# Kicker.net
KiCad netlist of a schematic drawn in EAGLE
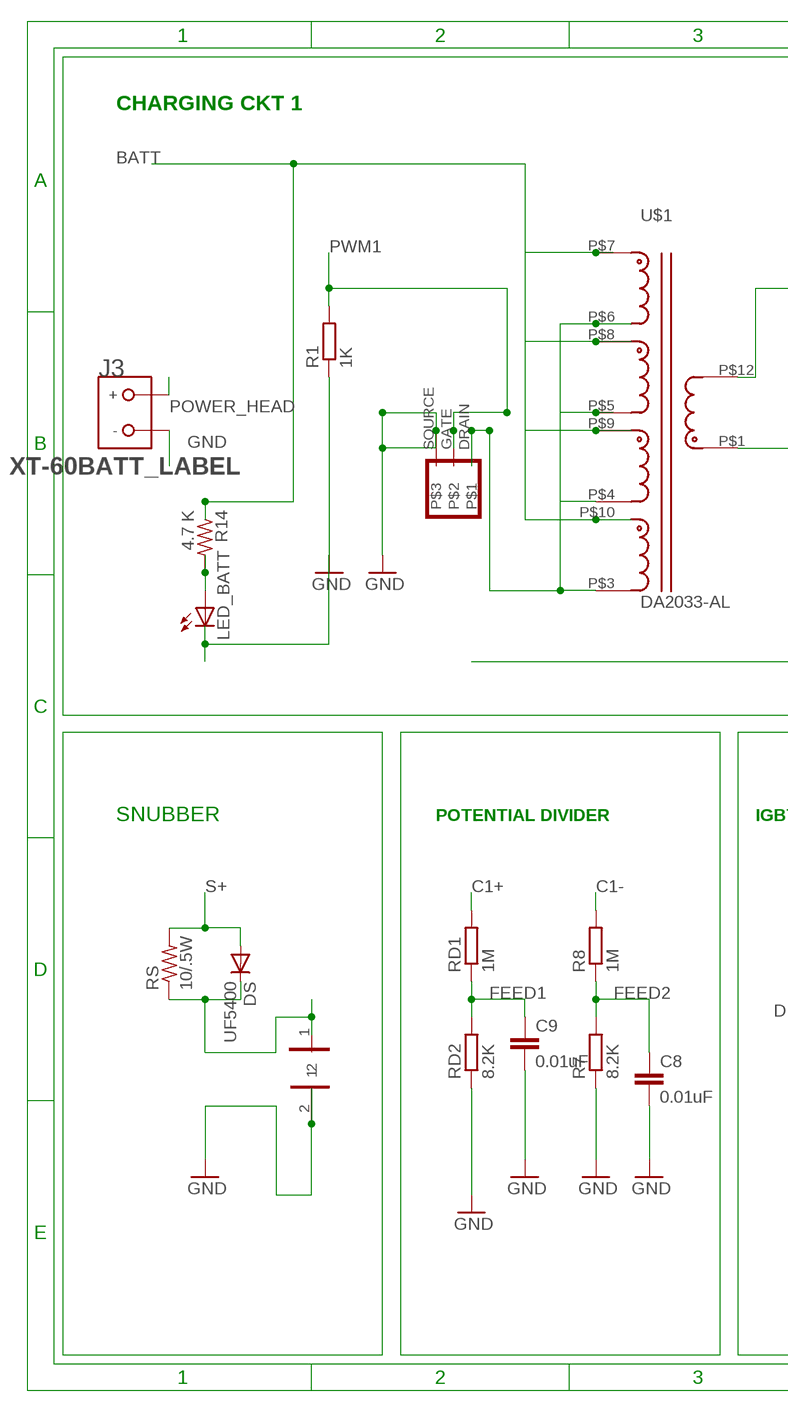
[diagram p0: schematic, sheet 1, part 1 of 2]
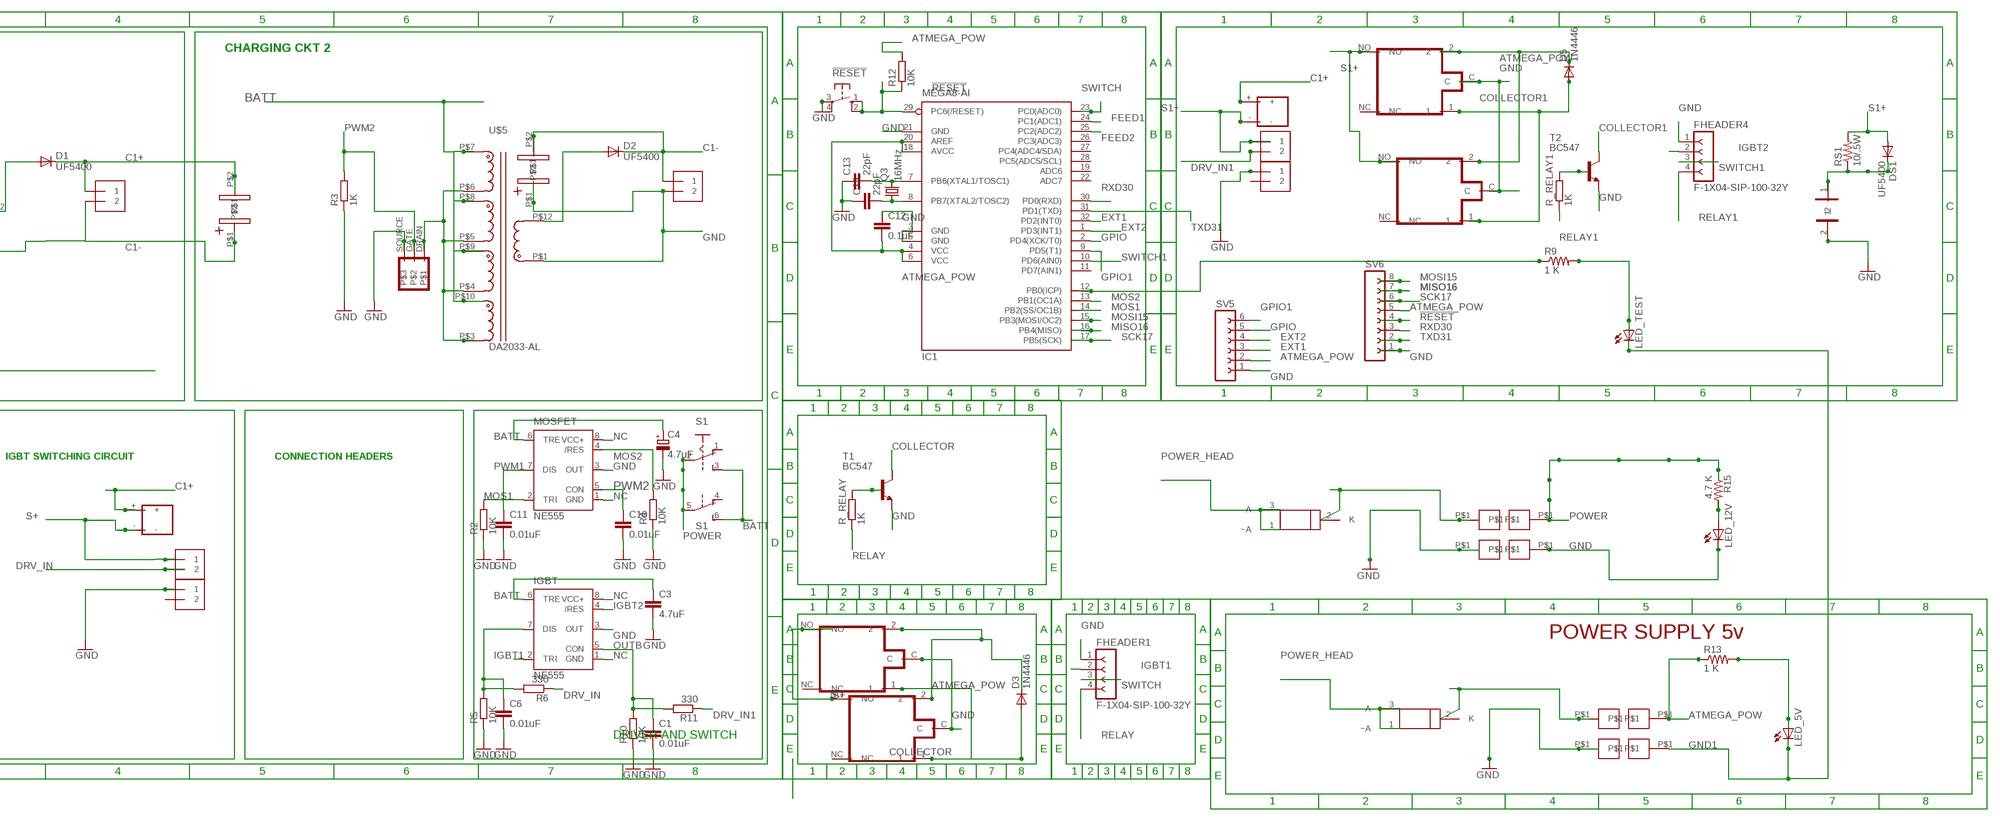
[diagram p1: schematic, sheet 1, part 2 of 2]

(export (version "E")
  (design (tool "Eeschema 10.0.6"))
  (components
    (comp (ref "!RESET")
      (value "10-XX")
      (footprint "eagle-import:B3F-10XX")
      (fields (field (name "MPN") "B3F-1000"))
      (libsource (lib "eagle-import") (part "10-XX"))
    )
    (comp (ref "5V")
      (value "PINHEAD_1")
      (footprint "eagle-import:PINHEAD_1")
      (libsource (lib "eagle-import") (part "PINHEAD_1"))
    )
    (comp (ref "C1")
      (value "0.01uF")
      (footprint "eagle-import:C1206")
      (libsource (lib "eagle-import") (part "C-EUC1206"))
    )
    (comp (ref "C3")
      (value "4.7uF")
      (footprint "eagle-import:C1206")
      (libsource (lib "eagle-import") (part "C-EUC1206"))
    )
    (comp (ref "C4")
      (value "4.7uF")
      (footprint "eagle-import:E2,5-6")
      (libsource (lib "eagle-import") (part "CPOL-EUE2.5-6"))
    )
    (comp (ref "C6")
      (value "0.01uF")
      (footprint "eagle-import:C1206")
      (libsource (lib "eagle-import") (part "C-EUC1206"))
    )
    (comp (ref "C8")
      (value "0.01uF")
      (footprint "eagle-import:C1206")
      (libsource (lib "eagle-import") (part "C-EUC1206"))
    )
    (comp (ref "C9")
      (value "0.01uF")
      (footprint "eagle-import:C1206")
      (libsource (lib "eagle-import") (part "C-EUC1206"))
    )
    (comp (ref "C10")
      (value "0.01uF")
      (footprint "eagle-import:C1206")
      (libsource (lib "eagle-import") (part "C-EUC1206"))
    )
    (comp (ref "C11")
      (value "0.01uF")
      (footprint "eagle-import:C1206")
      (libsource (lib "eagle-import") (part "C-EUC1206"))
    )
    (comp (ref "C12")
      (value "0.1uF")
      (footprint "eagle-import:C1206")
      (libsource (lib "eagle-import") (part "C-EUC1206"))
    )
    (comp (ref "C13")
      (value "22pF")
      (footprint "eagle-import:C1206")
      (libsource (lib "eagle-import") (part "C-EUC1206"))
    )
    (comp (ref "C14")
      (value "22pF")
      (footprint "eagle-import:C1206")
      (libsource (lib "eagle-import") (part "C-EUC1206"))
    )
    (comp (ref "D1")
      (value "UF5400")
      (footprint "eagle-import:DO201-15")
      (libsource (lib "eagle-import") (part "UF5400"))
    )
    (comp (ref "D2")
      (value "UF5400")
      (footprint "eagle-import:DO201-15")
      (libsource (lib "eagle-import") (part "UF5400"))
    )
    (comp (ref "D3")
      (value "1N4446")
      (footprint "eagle-import:DO35-10")
      (libsource (lib "eagle-import") (part "1N4446"))
    )
    (comp (ref "D5")
      (value "1N4446")
      (footprint "eagle-import:DO35-10")
      (libsource (lib "eagle-import") (part "1N4446"))
    )
    (comp (ref "DS")
      (value "UF5400")
      (footprint "eagle-import:DO201-15")
      (libsource (lib "eagle-import") (part "UF5400"))
    )
    (comp (ref "DS1")
      (value "UF5400")
      (footprint "eagle-import:DO201-15")
      (libsource (lib "eagle-import") (part "UF5400"))
    )
    (comp (ref "FHEADER1")
      (value "F-1X04-SIP-100-32Y")
      (footprint "eagle-import:SIP-100-04-32Y")
      (libsource (lib "eagle-import") (part "F-1X04-SIP-100-32Y"))
    )
    (comp (ref "FHEADER4")
      (value "F-1X04-SIP-100-32Y")
      (footprint "eagle-import:SIP-100-04-32Y")
      (libsource (lib "eagle-import") (part "F-1X04-SIP-100-32Y"))
    )
    (comp (ref "GND")
      (value "PINHEAD_1")
      (footprint "eagle-import:PINHEAD_1")
      (libsource (lib "eagle-import") (part "PINHEAD_1"))
    )
    (comp (ref "GND12")
      (value "PINHEAD_1")
      (footprint "eagle-import:PINHEAD_1")
      (libsource (lib "eagle-import") (part "PINHEAD_1"))
    )
    (comp (ref "GND_5V")
      (value "PINHEAD_1")
      (footprint "eagle-import:PINHEAD_1")
      (libsource (lib "eagle-import") (part "PINHEAD_1"))
    )
    (comp (ref "GND_12V1")
      (value "PINHEAD_1")
      (footprint "eagle-import:PINHEAD_1")
      (libsource (lib "eagle-import") (part "PINHEAD_1"))
    )
    (comp (ref "IC1")
      (value "MEGA8-AI")
      (footprint "eagle-import:TQFP32-08")
      (fields (field (name "MPN") "ATMEGA8-16AU"))
      (libsource (lib "eagle-import") (part "MEGA8-AI"))
    )
    (comp (ref "IGBT")
      (value "NE555")
      (footprint "eagle-import:DIL-08")
      (fields (field (name "MF") "Arrow Electronics") (field (name "MPN") "NE555N"))
      (libsource (lib "eagle-import") (part "NE555"))
    )
    (comp (ref "J1")
      (value "1X2-3.5MM")
      (footprint "eagle-import:1X2-3.5MM")
      (libsource (lib "eagle-import") (part "1X2-3.5MM"))
    )
    (comp (ref "J2")
      (value "1X2-3.5MM")
      (footprint "eagle-import:1X2-3.5MM")
      (libsource (lib "eagle-import") (part "1X2-3.5MM"))
    )
    (comp (ref "J3")
      (value "XT-60BATT_LABEL")
      (footprint "eagle-import:XT-60")
      (libsource (lib "eagle-import") (part "XT-60BATT_LABEL"))
    )
    (comp (ref "J4")
      (value "1X2-3.5MM")
      (footprint "eagle-import:1X2-3.5MM")
      (libsource (lib "eagle-import") (part "1X2-3.5MM"))
    )
    (comp (ref "J5")
      (value "1X2-3.5MM")
      (footprint "eagle-import:1X2-3.5MM")
      (libsource (lib "eagle-import") (part "1X2-3.5MM"))
    )
    (comp (ref "J6")
      (value "1X2-3.5MM")
      (footprint "eagle-import:1X2-3.5MM")
      (libsource (lib "eagle-import") (part "1X2-3.5MM"))
    )
    (comp (ref "J7")
      (value "1X2-3.5MM")
      (footprint "eagle-import:1X2-3.5MM")
      (libsource (lib "eagle-import") (part "1X2-3.5MM"))
    )
    (comp (ref "LED_5V")
      (value "LEDSML1206")
      (footprint "eagle-import:SML1206")
      (libsource (lib "eagle-import") (part "LEDSML1206"))
    )
    (comp (ref "LED_12V")
      (value "LEDSML1206")
      (footprint "eagle-import:SML1206")
      (libsource (lib "eagle-import") (part "LEDSML1206"))
    )
    (comp (ref "LED_BATT")
      (value "LEDSML1206")
      (footprint "eagle-import:SML1206")
      (libsource (lib "eagle-import") (part "LEDSML1206"))
    )
    (comp (ref "LED_TEST")
      (value "LEDSML1206")
      (footprint "eagle-import:SML1206")
      (libsource (lib "eagle-import") (part "LEDSML1206"))
    )
    (comp (ref "MOSFET")
      (value "NE555")
      (footprint "eagle-import:DIL-08")
      (fields (field (name "MF") "Arrow Electronics") (field (name "MPN") "NE555N"))
      (libsource (lib "eagle-import") (part "NE555"))
    )
    (comp (ref "POWER_1")
      (value "PINHEAD_1")
      (footprint "eagle-import:PINHEAD_1")
      (libsource (lib "eagle-import") (part "PINHEAD_1"))
    )
    (comp (ref "POWER_HEAD1")
      (value "PINHEAD_1")
      (footprint "eagle-import:PINHEAD_1")
      (libsource (lib "eagle-import") (part "PINHEAD_1"))
    )
    (comp (ref "Q3")
      (value "16MHz")
      (footprint "eagle-import:HC49U70")
      (libsource (lib "eagle-import") (part "CRYSTALHC49U70"))
    )
    (comp (ref "R1")
      (value "1K")
      (footprint "eagle-import:R1206")
      (libsource (lib "eagle-import") (part "R-EU_R1206"))
    )
    (comp (ref "R2")
      (value "10K")
      (footprint "eagle-import:R1206")
      (libsource (lib "eagle-import") (part "R-EU_R1206"))
    )
    (comp (ref "R3")
      (value "1K")
      (footprint "eagle-import:R1206")
      (libsource (lib "eagle-import") (part "R-EU_R1206"))
    )
    (comp (ref "R4")
      (value "10K")
      (footprint "eagle-import:R1206")
      (libsource (lib "eagle-import") (part "R-EU_R1206"))
    )
    (comp (ref "R5")
      (value "10K")
      (footprint "eagle-import:R1206")
      (libsource (lib "eagle-import") (part "R-EU_R1206"))
    )
    (comp (ref "R6")
      (value "330")
      (footprint "eagle-import:R1206")
      (libsource (lib "eagle-import") (part "R-EU_R1206"))
    )
    (comp (ref "R7")
      (value "8.2K")
      (footprint "eagle-import:R1206")
      (libsource (lib "eagle-import") (part "R-EU_R1206"))
    )
    (comp (ref "R8")
      (value "1M")
      (footprint "eagle-import:R1206")
      (libsource (lib "eagle-import") (part "R-EU_R1206"))
    )
    (comp (ref "R9")
      (value "1 K")
      (footprint "eagle-import:0805-THM")
      (libsource (lib "eagle-import") (part "FLIPFLOP-RES"))
    )
    (comp (ref "R10")
      (value "10K")
      (footprint "eagle-import:R1206")
      (libsource (lib "eagle-import") (part "R-EU_R1206"))
    )
    (comp (ref "R11")
      (value "330")
      (footprint "eagle-import:R1206")
      (libsource (lib "eagle-import") (part "R-EU_R1206"))
    )
    (comp (ref "R12")
      (value "10K")
      (footprint "eagle-import:R1206")
      (libsource (lib "eagle-import") (part "R-EU_R1206"))
    )
    (comp (ref "R13")
      (value "1 K")
      (footprint "eagle-import:0805-THM")
      (libsource (lib "eagle-import") (part "FLIPFLOP-RES"))
    )
    (comp (ref "R14")
      (value "4.7 K")
      (footprint "eagle-import:0805-THM")
      (libsource (lib "eagle-import") (part "FLIPFLOP-RES"))
    )
    (comp (ref "R15")
      (value "4.7 K")
      (footprint "eagle-import:0805-THM")
      (libsource (lib "eagle-import") (part "FLIPFLOP-RES"))
    )
    (comp (ref "RD1")
      (value "1M")
      (footprint "eagle-import:R1206")
      (libsource (lib "eagle-import") (part "R-EU_R1206"))
    )
    (comp (ref "RD2")
      (value "8.2K")
      (footprint "eagle-import:R1206")
      (libsource (lib "eagle-import") (part "R-EU_R1206"))
    )
    (comp (ref "RS")
      (value "10/.5W")
      (footprint "eagle-import:0411_15")
      (libsource (lib "eagle-import") (part "R-US_0411/15"))
    )
    (comp (ref "RS1")
      (value "10/.5W")
      (footprint "eagle-import:0411_15")
      (libsource (lib "eagle-import") (part "R-US_0411/15"))
    )
    (comp (ref "R_RELAY")
      (value "1K")
      (footprint "eagle-import:R1206")
      (libsource (lib "eagle-import") (part "R-EU_R1206"))
    )
    (comp (ref "R_RELAY1")
      (value "1K")
      (footprint "eagle-import:R1206")
      (libsource (lib "eagle-import") (part "R-EU_R1206"))
    )
    (comp (ref "S1")
      (value "A68-A31")
      (footprint "eagle-import:A68-A31")
      (libsource (lib "eagle-import") (part "A68-A31"))
    )
    (comp (ref "SV5")
      (value "FE06-1")
      (footprint "eagle-import:FE06")
      (libsource (lib "eagle-import") (part "FE06-1"))
    )
    (comp (ref "SV6")
      (value "FE08-1")
      (footprint "eagle-import:FE08")
      (libsource (lib "eagle-import") (part "FE08-1"))
    )
    (comp (ref "T1")
      (value "BC547")
      (footprint "eagle-import:TO92")
      (libsource (lib "eagle-import") (part "BC547"))
    )
    (comp (ref "T2")
      (value "BC547")
      (footprint "eagle-import:TO92")
      (libsource (lib "eagle-import") (part "BC547"))
    )
    (comp (ref "U$1")
      (value "DA2033-AL")
      (footprint "eagle-import:DA2033-AL")
      (libsource (lib "eagle-import") (part "DA2033-AL"))
    )
    (comp (ref "U$2")
      (value "CAPS")
      (footprint "eagle-import:CAP")
      (libsource (lib "eagle-import") (part "CAPS"))
    )
    (comp (ref "U$3")
      (value "MOS")
      (footprint "eagle-import:MOS")
      (libsource (lib "eagle-import") (part "MOS"))
    )
    (comp (ref "U$4")
      (value "CAPS")
      (footprint "eagle-import:CAP")
      (libsource (lib "eagle-import") (part "CAPS"))
    )
    (comp (ref "U$5")
      (value "DA2033-AL")
      (footprint "eagle-import:DA2033-AL")
      (libsource (lib "eagle-import") (part "DA2033-AL"))
    )
    (comp (ref "U$6")
      (value "SCREW")
      (footprint "eagle-import:SCREW")
      (libsource (lib "eagle-import") (part "SCREW"))
    )
    (comp (ref "U$7")
      (value "POLYCAP")
      (footprint "eagle-import:POLYCAP")
      (libsource (lib "eagle-import") (part "POLYCAP"))
    )
    (comp (ref "U$8")
      (value "POLYCAP")
      (footprint "eagle-import:POLYCAP")
      (libsource (lib "eagle-import") (part "POLYCAP"))
    )
    (comp (ref "U$9")
      (value "MOS")
      (footprint "eagle-import:MOS")
      (libsource (lib "eagle-import") (part "MOS"))
    )
    (comp (ref "U$10")
      (value "REL")
      (footprint "eagle-import:REL")
      (libsource (lib "eagle-import") (part "REL"))
    )
    (comp (ref "U$11")
      (value "REL")
      (footprint "eagle-import:REL")
      (libsource (lib "eagle-import") (part "REL"))
    )
    (comp (ref "U$12")
      (value "REL")
      (footprint "eagle-import:REL")
      (libsource (lib "eagle-import") (part "REL"))
    )
    (comp (ref "U$13")
      (value "REL")
      (footprint "eagle-import:REL")
      (libsource (lib "eagle-import") (part "REL"))
    )
    (comp (ref "U$16")
      (value "SCREW")
      (footprint "eagle-import:SCREW")
      (libsource (lib "eagle-import") (part "SCREW"))
    )
    (comp (ref "U1")
      (value "LP38690DT-3.3")
      (footprint "eagle-import:TO228P1042X238-3N")
      (libsource (lib "eagle-import") (part "LP38690DT-3.3"))
    )
    (comp (ref "U4")
      (value "LP38690DT-3.3")
      (footprint "eagle-import:TO228P1042X238-3N")
      (libsource (lib "eagle-import") (part "LP38690DT-3.3"))
    )
    (comp (ref "V_BAT")
      (value "PINHEAD_1")
      (footprint "eagle-import:PINHEAD_1")
      (libsource (lib "eagle-import") (part "PINHEAD_1"))
    )
  )
  (nets
    (net (code "1") (name "/ATMEGA_POW") (class "Default")
      (node (ref "5V") (pin "P$1") (pinfunction "P$1_P$1") (pintype "bidirectional"))
      (node (ref "C12") (pin "2") (pinfunction "2_2") (pintype "passive"))
      (node (ref "D3") (pin "C") (pinfunction "C_C") (pintype "passive"))
      (node (ref "D5") (pin "C") (pinfunction "C_C") (pintype "passive"))
      (node (ref "IC1") (pin "18") (pinfunction "AVCC_18") (pintype "power_in"))
      (node (ref "IC1") (pin "20") (pinfunction "AREF_20") (pintype "passive"))
      (node (ref "IC1") (pin "4") (pinfunction "VCC_4") (pintype "power_in"))
      (node (ref "IC1") (pin "6") (pinfunction "VCC_6") (pintype "power_in"))
      (node (ref "R12") (pin "2") (pinfunction "2_2") (pintype "passive"))
      (node (ref "R13") (pin "1") (pinfunction "1_1") (pintype "passive"))
      (node (ref "SV5") (pin "2") (pinfunction "2_2") (pintype "passive"))
      (node (ref "SV6") (pin "5") (pinfunction "5_5") (pintype "passive"))
      (node (ref "U$10") (pin "2") (pinfunction "2_2") (pintype "bidirectional"))
      (node (ref "U$11") (pin "2") (pinfunction "2_2") (pintype "bidirectional"))
      (node (ref "U$12") (pin "2") (pinfunction "2_2") (pintype "bidirectional"))
      (node (ref "U$13") (pin "2") (pinfunction "2_2") (pintype "bidirectional"))
    )
    (net (code "2") (name "/BATT") (class "Default")
      (node (ref "C3") (pin "1") (pinfunction "1_1") (pintype "passive"))
      (node (ref "C4") (pin "+") (pinfunction "+_+") (pintype "passive"))
      (node (ref "IGBT") (pin "6") (pinfunction "TRE_6") (pintype "input"))
      (node (ref "MOSFET") (pin "6") (pinfunction "TRE_6") (pintype "input"))
      (node (ref "R14") (pin "1") (pinfunction "1_1") (pintype "passive"))
      (node (ref "S1") (pin "3") (pinfunction "S_3") (pintype "passive"))
      (node (ref "S1") (pin "6") (pinfunction "S_6") (pintype "passive"))
      (node (ref "U$1") (pin "P$10") (pinfunction "10_P$10") (pintype "passive"))
      (node (ref "U$1") (pin "P$7") (pinfunction "7_P$7") (pintype "passive"))
      (node (ref "U$1") (pin "P$8") (pinfunction "8_P$8") (pintype "passive"))
      (node (ref "U$1") (pin "P$9") (pinfunction "9_P$9") (pintype "passive"))
      (node (ref "U$5") (pin "P$10") (pinfunction "10_P$10") (pintype "passive"))
      (node (ref "U$5") (pin "P$7") (pinfunction "7_P$7") (pintype "passive"))
      (node (ref "U$5") (pin "P$8") (pinfunction "8_P$8") (pintype "passive"))
      (node (ref "U$5") (pin "P$9") (pinfunction "9_P$9") (pintype "passive"))
    )
    (net (code "3") (name "/C1+") (class "Default")
      (node (ref "D1") (pin "C") (pinfunction "C_C") (pintype "passive"))
      (node (ref "J2") (pin "1") (pinfunction "1_1") (pintype "passive"))
      (node (ref "RD1") (pin "2") (pinfunction "2_2") (pintype "passive"))
      (node (ref "U$16") (pin "+") (pinfunction "+_+") (pintype "bidirectional"))
      (node (ref "U$2") (pin "P$2") (pinfunction "P$2_P$2") (pintype "bidirectional"))
      (node (ref "U$6") (pin "+") (pinfunction "+_+") (pintype "bidirectional"))
    )
    (net (code "4") (name "/C1-") (class "Default")
      (node (ref "D2") (pin "C") (pinfunction "C_C") (pintype "passive"))
      (node (ref "J1") (pin "1") (pinfunction "1_1") (pintype "passive"))
      (node (ref "J2") (pin "2") (pinfunction "2_2") (pintype "passive"))
      (node (ref "R8") (pin "2") (pinfunction "2_2") (pintype "passive"))
      (node (ref "U$1") (pin "P$1") (pinfunction "1_P$1") (pintype "passive"))
      (node (ref "U$2") (pin "P$1") (pinfunction "P$1_P$1") (pintype "bidirectional"))
      (node (ref "U$4") (pin "P$2") (pinfunction "P$2_P$2") (pintype "bidirectional"))
    )
    (net (code "5") (name "/COLLECTOR") (class "Default")
      (node (ref "D3") (pin "A") (pinfunction "A_A") (pintype "passive"))
      (node (ref "T1") (pin "3") (pinfunction "C_3") (pintype "passive"))
      (node (ref "U$10") (pin "1") (pinfunction "1_1") (pintype "bidirectional"))
      (node (ref "U$12") (pin "1") (pinfunction "1_1") (pintype "bidirectional"))
    )
    (net (code "6") (name "/COLLECTOR1") (class "Default")
      (node (ref "D5") (pin "A") (pinfunction "A_A") (pintype "passive"))
      (node (ref "T2") (pin "3") (pinfunction "C_3") (pintype "passive"))
      (node (ref "U$11") (pin "1") (pinfunction "1_1") (pintype "bidirectional"))
      (node (ref "U$13") (pin "1") (pinfunction "1_1") (pintype "bidirectional"))
    )
    (net (code "7") (name "/DRV_IN") (class "Default")
      (node (ref "J6") (pin "2") (pinfunction "2_2") (pintype "passive"))
      (node (ref "R6") (pin "1") (pinfunction "1_1") (pintype "passive"))
    )
    (net (code "8") (name "/DRV_IN1") (class "Default")
      (node (ref "J4") (pin "2") (pinfunction "2_2") (pintype "passive"))
      (node (ref "R11") (pin "1") (pinfunction "1_1") (pintype "passive"))
    )
    (net (code "9") (name "/EXT1") (class "Default")
      (node (ref "IC1") (pin "32") (pinfunction "PD2(INT0)_32") (pintype "bidirectional"))
      (node (ref "SV5") (pin "3") (pinfunction "3_3") (pintype "passive"))
    )
    (net (code "10") (name "/EXT2") (class "Default")
      (node (ref "IC1") (pin "1") (pinfunction "PD3(INT1)_1") (pintype "bidirectional"))
      (node (ref "SV5") (pin "4") (pinfunction "4_4") (pintype "passive"))
    )
    (net (code "11") (name "/FEED1") (class "Default")
      (node (ref "C9") (pin "1") (pinfunction "1_1") (pintype "passive"))
      (node (ref "IC1") (pin "24") (pinfunction "PC1(ADC1)_24") (pintype "bidirectional"))
      (node (ref "RD1") (pin "1") (pinfunction "1_1") (pintype "passive"))
      (node (ref "RD2") (pin "2") (pinfunction "2_2") (pintype "passive"))
    )
    (net (code "12") (name "/FEED2") (class "Default")
      (node (ref "C8") (pin "1") (pinfunction "1_1") (pintype "passive"))
      (node (ref "IC1") (pin "25") (pinfunction "PC2(ADC2)_25") (pintype "bidirectional"))
      (node (ref "R7") (pin "2") (pinfunction "2_2") (pintype "passive"))
      (node (ref "R8") (pin "1") (pinfunction "1_1") (pintype "passive"))
    )
    (net (code "13") (name "/GND1") (class "Default")
      (node (ref "GND") (pin "P$1") (pinfunction "P$1_P$1") (pintype "bidirectional"))
      (node (ref "LED_5V") (pin "C") (pinfunction "C_C") (pintype "passive"))
      (node (ref "LED_TEST") (pin "C") (pinfunction "C_C") (pintype "passive"))
    )
    (net (code "14") (name "/GPIO") (class "Default")
      (node (ref "IC1") (pin "2") (pinfunction "PD4(XCK/T0)_2") (pintype "bidirectional"))
      (node (ref "SV5") (pin "5") (pinfunction "5_5") (pintype "passive"))
    )
    (net (code "15") (name "/GPIO1") (class "Default")
      (node (ref "IC1") (pin "9") (pinfunction "PD5(T1)_9") (pintype "bidirectional"))
      (node (ref "SV5") (pin "6") (pinfunction "6_6") (pintype "passive"))
    )
    (net (code "16") (name "/IGBT1") (class "Default")
      (node (ref "FHEADER1") (pin "2") (pinfunction "2_2") (pintype "passive"))
      (node (ref "IGBT") (pin "2") (pinfunction "TRI_2") (pintype "input"))
    )
    (net (code "17") (name "/IGBT2") (class "Default")
      (node (ref "FHEADER4") (pin "2") (pinfunction "2_2") (pintype "passive"))
      (node (ref "IGBT") (pin "4") (pinfunction "/RES_4") (pintype "input"))
    )
    (net (code "18") (name "/MISO16") (class "Default")
      (node (ref "IC1") (pin "16") (pinfunction "PB4(MISO)_16") (pintype "bidirectional"))
      (node (ref "SV6") (pin "7") (pinfunction "7_7") (pintype "passive"))
    )
    (net (code "19") (name "/MOS1") (class "Default")
      (node (ref "IC1") (pin "14") (pinfunction "PB2(SS/OC1B)_14") (pintype "bidirectional"))
      (node (ref "MOSFET") (pin "2") (pinfunction "TRI_2") (pintype "input"))
      (node (ref "R2") (pin "2") (pinfunction "2_2") (pintype "passive"))
    )
    (net (code "20") (name "/MOS2") (class "Default")
      (node (ref "IC1") (pin "13") (pinfunction "PB1(OC1A)_13") (pintype "bidirectional"))
      (node (ref "MOSFET") (pin "4") (pinfunction "/RES_4") (pintype "input"))
      (node (ref "R4") (pin "2") (pinfunction "2_2") (pintype "passive"))
    )
    (net (code "21") (name "/MOSI15") (class "Default")
      (node (ref "IC1") (pin "15") (pinfunction "PB3(MOSI/OC2)_15") (pintype "bidirectional"))
      (node (ref "SV6") (pin "8") (pinfunction "8_8") (pintype "passive"))
    )
    (net (code "22") (name "/NC") (class "Default")
      (node (ref "IGBT") (pin "1") (pinfunction "GND_1") (pintype "power_in"))
      (node (ref "IGBT") (pin "8") (pinfunction "VCC+_8") (pintype "power_in"))
      (node (ref "MOSFET") (pin "1") (pinfunction "GND_1") (pintype "power_in"))
      (node (ref "MOSFET") (pin "8") (pinfunction "VCC+_8") (pintype "power_in"))
    )
    (net (code "23") (name "/OUTB") (class "Default")
      (node (ref "C1") (pin "1") (pinfunction "1_1") (pintype "passive"))
      (node (ref "IGBT") (pin "5") (pinfunction "CON_5") (pintype "input"))
      (node (ref "R10") (pin "2") (pinfunction "2_2") (pintype "passive"))
      (node (ref "R11") (pin "2") (pinfunction "2_2") (pintype "passive"))
    )
    (net (code "24") (name "/POWER") (class "Default")
      (node (ref "POWER_1") (pin "P$1") (pinfunction "P$1_P$1") (pintype "bidirectional"))
      (node (ref "R15") (pin "1") (pinfunction "1_1") (pintype "passive"))
      (node (ref "S1") (pin "2") (pinfunction "P_2") (pintype "passive"))
      (node (ref "S1") (pin "5") (pinfunction "P_5") (pintype "passive"))
    )
    (net (code "25") (name "/POWER_HEAD") (class "Default")
      (node (ref "J3") (pin "BATT") (pinfunction "+_BATT") (pintype "passive"))
      (node (ref "U1") (pin "1") (pinfunction "~{A}_1") (pintype "bidirectional"))
      (node (ref "U1") (pin "3") (pinfunction "A_3") (pintype "bidirectional"))
      (node (ref "U4") (pin "1") (pinfunction "~{A}_1") (pintype "bidirectional"))
      (node (ref "U4") (pin "3") (pinfunction "A_3") (pintype "bidirectional"))
    )
    (net (code "26") (name "/PWM1") (class "Default")
      (node (ref "C11") (pin "1") (pinfunction "1_1") (pintype "passive"))
      (node (ref "MOSFET") (pin "7") (pinfunction "DIS_7") (pintype "input"))
      (node (ref "R1") (pin "2") (pinfunction "2_2") (pintype "passive"))
      (node (ref "U$3") (pin "GATE") (pinfunction "P$2_GATE") (pintype "bidirectional"))
    )
    (net (code "27") (name "/PWM2") (class "Default")
      (node (ref "C10") (pin "1") (pinfunction "1_1") (pintype "passive"))
      (node (ref "MOSFET") (pin "5") (pinfunction "CON_5") (pintype "input"))
      (node (ref "R3") (pin "2") (pinfunction "2_2") (pintype "passive"))
      (node (ref "U$9") (pin "GATE") (pinfunction "P$2_GATE") (pintype "bidirectional"))
    )
    (net (code "28") (name "/RELAY") (class "Default")
      (node (ref "FHEADER1") (pin "4") (pinfunction "4_4") (pintype "passive"))
      (node (ref "R_RELAY") (pin "1") (pinfunction "1_1") (pintype "passive"))
    )
    (net (code "29") (name "/RELAY1") (class "Default")
      (node (ref "FHEADER4") (pin "4") (pinfunction "4_4") (pintype "passive"))
      (node (ref "R_RELAY1") (pin "1") (pinfunction "1_1") (pintype "passive"))
    )
    (net (code "30") (name "/RXD30") (class "Default")
      (node (ref "IC1") (pin "30") (pinfunction "PD0(RXD)_30") (pintype "bidirectional"))
      (node (ref "SV6") (pin "3") (pinfunction "3_3") (pintype "passive"))
    )
    (net (code "31") (name "/S+") (class "Default")
      (node (ref "DS") (pin "A") (pinfunction "A_A") (pintype "passive"))
      (node (ref "J6") (pin "1") (pinfunction "1_1") (pintype "passive"))
      (node (ref "RS") (pin "2") (pinfunction "2_2") (pintype "passive"))
      (node (ref "U$10") (pin "NO") (pinfunction "NO_NO") (pintype "bidirectional"))
      (node (ref "U$12") (pin "NO") (pinfunction "NO_NO") (pintype "bidirectional"))
      (node (ref "U$16") (pin "-") (pinfunction "-_-") (pintype "bidirectional"))
    )
    (net (code "32") (name "/S1+") (class "Default")
      (node (ref "DS1") (pin "A") (pinfunction "A_A") (pintype "passive"))
      (node (ref "J4") (pin "1") (pinfunction "1_1") (pintype "passive"))
      (node (ref "RS1") (pin "2") (pinfunction "2_2") (pintype "passive"))
      (node (ref "U$11") (pin "NO") (pinfunction "NO_NO") (pintype "bidirectional"))
      (node (ref "U$13") (pin "NO") (pinfunction "NO_NO") (pintype "bidirectional"))
      (node (ref "U$6") (pin "-") (pinfunction "-_-") (pintype "bidirectional"))
    )
    (net (code "33") (name "/SCK17") (class "Default")
      (node (ref "IC1") (pin "17") (pinfunction "PB5(SCK)_17") (pintype "bidirectional"))
      (node (ref "SV6") (pin "6") (pinfunction "6_6") (pintype "passive"))
    )
    (net (code "34") (name "/SWITCH") (class "Default")
      (node (ref "FHEADER1") (pin "3") (pinfunction "3_3") (pintype "passive"))
      (node (ref "IC1") (pin "23") (pinfunction "PC0(ADC0)_23") (pintype "bidirectional"))
    )
    (net (code "35") (name "/SWITCH1") (class "Default")
      (node (ref "FHEADER4") (pin "3") (pinfunction "3_3") (pintype "passive"))
      (node (ref "IC1") (pin "10") (pinfunction "PD6(AIN0)_10") (pintype "bidirectional"))
    )
    (net (code "36") (name "/TXD31") (class "Default")
      (node (ref "IC1") (pin "31") (pinfunction "PD1(TXD)_31") (pintype "bidirectional"))
      (node (ref "SV6") (pin "2") (pinfunction "2_2") (pintype "passive"))
    )
    (net (code "37") (name "/~{RESET}") (class "Default")
      (node (ref "!RESET") (pin "1") (pinfunction "S_1") (pintype "passive"))
      (node (ref "!RESET") (pin "2") (pinfunction "S1_2") (pintype "passive"))
      (node (ref "IC1") (pin "29") (pinfunction "PC6(/RESET)_29") (pintype "bidirectional"))
      (node (ref "R12") (pin "1") (pinfunction "1_1") (pintype "passive"))
      (node (ref "SV6") (pin "4") (pinfunction "4_4") (pintype "passive"))
    )
    (net (code "38") (name "GND") (class "Default")
      (node (ref "!RESET") (pin "3") (pinfunction "P_3") (pintype "passive"))
      (node (ref "!RESET") (pin "4") (pinfunction "P1_4") (pintype "passive"))
      (node (ref "C1") (pin "2") (pinfunction "2_2") (pintype "passive"))
      (node (ref "C10") (pin "2") (pinfunction "2_2") (pintype "passive"))
      (node (ref "C11") (pin "2") (pinfunction "2_2") (pintype "passive"))
      (node (ref "C12") (pin "1") (pinfunction "1_1") (pintype "passive"))
      (node (ref "C13") (pin "1") (pinfunction "1_1") (pintype "passive"))
      (node (ref "C14") (pin "1") (pinfunction "1_1") (pintype "passive"))
      (node (ref "C3") (pin "2") (pinfunction "2_2") (pintype "passive"))
      (node (ref "C4") (pin "-") (pinfunction "-_-") (pintype "passive"))
      (node (ref "C6") (pin "2") (pinfunction "2_2") (pintype "passive"))
      (node (ref "C8") (pin "2") (pinfunction "2_2") (pintype "passive"))
      (node (ref "C9") (pin "2") (pinfunction "2_2") (pintype "passive"))
      (node (ref "FHEADER1") (pin "1") (pinfunction "1_1") (pintype "passive"))
      (node (ref "FHEADER4") (pin "1") (pinfunction "1_1") (pintype "passive"))
      (node (ref "GND12") (pin "P$1") (pinfunction "P$1_P$1") (pintype "bidirectional"))
      (node (ref "GND_12V1") (pin "P$1") (pinfunction "P$1_P$1") (pintype "bidirectional"))
      (node (ref "GND_5V") (pin "P$1") (pinfunction "P$1_P$1") (pintype "bidirectional"))
      (node (ref "IC1") (pin "21") (pinfunction "GND_21") (pintype "power_in"))
      (node (ref "IC1") (pin "3") (pinfunction "GND_3") (pintype "power_in"))
      (node (ref "IC1") (pin "5") (pinfunction "GND_5") (pintype "power_in"))
      (node (ref "IGBT") (pin "3") (pinfunction "OUT_3") (pintype "output"))
      (node (ref "J1") (pin "2") (pinfunction "2_2") (pintype "passive"))
      (node (ref "J3") (pin "GND") (pinfunction "-_GND") (pintype "passive"))
      (node (ref "J5") (pin "1") (pinfunction "1_1") (pintype "passive"))
      (node (ref "J7") (pin "1") (pinfunction "1_1") (pintype "passive"))
      (node (ref "LED_12V") (pin "C") (pinfunction "C_C") (pintype "passive"))
      (node (ref "LED_BATT") (pin "C") (pinfunction "C_C") (pintype "passive"))
      (node (ref "MOSFET") (pin "3") (pinfunction "OUT_3") (pintype "output"))
      (node (ref "R1") (pin "1") (pinfunction "1_1") (pintype "passive"))
      (node (ref "R10") (pin "1") (pinfunction "1_1") (pintype "passive"))
      (node (ref "R2") (pin "1") (pinfunction "1_1") (pintype "passive"))
      (node (ref "R3") (pin "1") (pinfunction "1_1") (pintype "passive"))
      (node (ref "R4") (pin "1") (pinfunction "1_1") (pintype "passive"))
      (node (ref "R5") (pin "1") (pinfunction "1_1") (pintype "passive"))
      (node (ref "R7") (pin "1") (pinfunction "1_1") (pintype "passive"))
      (node (ref "RD2") (pin "1") (pinfunction "1_1") (pintype "passive"))
      (node (ref "SV5") (pin "1") (pinfunction "1_1") (pintype "passive"))
      (node (ref "SV6") (pin "1") (pinfunction "1_1") (pintype "passive"))
      (node (ref "T1") (pin "1") (pinfunction "E_1") (pintype "passive"))
      (node (ref "T2") (pin "1") (pinfunction "E_1") (pintype "passive"))
      (node (ref "U$10") (pin "C") (pinfunction "C_C") (pintype "bidirectional"))
      (node (ref "U$11") (pin "C") (pinfunction "C_C") (pintype "bidirectional"))
      (node (ref "U$12") (pin "C") (pinfunction "C_C") (pintype "bidirectional"))
      (node (ref "U$13") (pin "C") (pinfunction "C_C") (pintype "bidirectional"))
      (node (ref "U$3") (pin "SOURCE") (pinfunction "P$3_SOURCE") (pintype "bidirectional"))
      (node (ref "U$4") (pin "P$1") (pinfunction "P$1_P$1") (pintype "bidirectional"))
      (node (ref "U$5") (pin "P$1") (pinfunction "1_P$1") (pintype "passive"))
      (node (ref "U$7") (pin "2") (pinfunction "2_2") (pintype "bidirectional"))
      (node (ref "U$8") (pin "2") (pinfunction "2_2") (pintype "bidirectional"))
      (node (ref "U$9") (pin "SOURCE") (pinfunction "P$3_SOURCE") (pintype "bidirectional"))
    )
    (net (code "39") (name "Net-(DS-PadC)") (class "Default")
      (node (ref "DS") (pin "C") (pinfunction "C_C") (pintype "passive"))
      (node (ref "RS") (pin "1") (pinfunction "1_1") (pintype "passive"))
      (node (ref "U$7") (pin "1") (pinfunction "1_1") (pintype "bidirectional"))
    )
    (net (code "40") (name "Net-(DS1-PadC)") (class "Default")
      (node (ref "DS1") (pin "C") (pinfunction "C_C") (pintype "passive"))
      (node (ref "RS1") (pin "1") (pinfunction "1_1") (pintype "passive"))
      (node (ref "U$8") (pin "1") (pinfunction "1_1") (pintype "bidirectional"))
    )
    (net (code "41") (name "Net-(IC1-PB0(ICP))") (class "Default")
      (node (ref "IC1") (pin "12") (pinfunction "PB0(ICP)_12") (pintype "bidirectional"))
      (node (ref "R9") (pin "1") (pinfunction "1_1") (pintype "passive"))
    )
    (net (code "42") (name "Net-(IC1-PB6(XTAL1{slash}TOSC1))") (class "Default")
      (node (ref "C13") (pin "2") (pinfunction "2_2") (pintype "passive"))
      (node (ref "IC1") (pin "7") (pinfunction "PB6(XTAL1/TOSC1)_7") (pintype "bidirectional"))
      (node (ref "Q3") (pin "2") (pinfunction "2_2") (pintype "passive"))
    )
    (net (code "43") (name "Net-(IC1-PB7(XTAL2{slash}TOSC2))") (class "Default")
      (node (ref "C14") (pin "2") (pinfunction "2_2") (pintype "passive"))
      (node (ref "IC1") (pin "8") (pinfunction "PB7(XTAL2/TOSC2)_8") (pintype "bidirectional"))
      (node (ref "Q3") (pin "1") (pinfunction "1_1") (pintype "passive"))
    )
    (net (code "44") (name "Net-(IGBT-DIS)") (class "Default")
      (node (ref "C6") (pin "1") (pinfunction "1_1") (pintype "passive"))
      (node (ref "IGBT") (pin "7") (pinfunction "DIS_7") (pintype "input"))
      (node (ref "R5") (pin "2") (pinfunction "2_2") (pintype "passive"))
      (node (ref "R6") (pin "2") (pinfunction "2_2") (pintype "passive"))
    )
    (net (code "45") (name "Net-(LED_5V-PadA)") (class "Default")
      (node (ref "LED_5V") (pin "A") (pinfunction "A_A") (pintype "passive"))
      (node (ref "R13") (pin "2") (pinfunction "2_2") (pintype "passive"))
    )
    (net (code "46") (name "Net-(LED_12V-PadA)") (class "Default")
      (node (ref "LED_12V") (pin "A") (pinfunction "A_A") (pintype "passive"))
      (node (ref "R15") (pin "2") (pinfunction "2_2") (pintype "passive"))
    )
    (net (code "47") (name "Net-(LED_BATT-PadA)") (class "Default")
      (node (ref "LED_BATT") (pin "A") (pinfunction "A_A") (pintype "passive"))
      (node (ref "R14") (pin "2") (pinfunction "2_2") (pintype "passive"))
    )
    (net (code "48") (name "Net-(LED_TEST-PadA)") (class "Default")
      (node (ref "LED_TEST") (pin "A") (pinfunction "A_A") (pintype "passive"))
      (node (ref "R9") (pin "2") (pinfunction "2_2") (pintype "passive"))
    )
    (net (code "49") (name "Net-(T1-B)") (class "Default")
      (node (ref "R_RELAY") (pin "2") (pinfunction "2_2") (pintype "passive"))
      (node (ref "T1") (pin "2") (pinfunction "B_2") (pintype "passive"))
    )
    (net (code "50") (name "Net-(T2-B)") (class "Default")
      (node (ref "R_RELAY1") (pin "2") (pinfunction "2_2") (pintype "passive"))
      (node (ref "T2") (pin "2") (pinfunction "B_2") (pintype "passive"))
    )
    (net (code "51") (name "Net-(U$1-3)") (class "Default")
      (node (ref "U$1") (pin "P$3") (pinfunction "3_P$3") (pintype "passive"))
      (node (ref "U$1") (pin "P$4") (pinfunction "4_P$4") (pintype "passive"))
      (node (ref "U$1") (pin "P$5") (pinfunction "5_P$5") (pintype "passive"))
      (node (ref "U$1") (pin "P$6") (pinfunction "6_P$6") (pintype "passive"))
      (node (ref "U$3") (pin "DRAIN") (pinfunction "P$1_DRAIN") (pintype "bidirectional"))
    )
    (net (code "52") (name "Net-(U$1-12)") (class "Default")
      (node (ref "D1") (pin "A") (pinfunction "A_A") (pintype "passive"))
      (node (ref "U$1") (pin "P$12") (pinfunction "12_P$12") (pintype "passive"))
    )
    (net (code "53") (name "Net-(U$5-3)") (class "Default")
      (node (ref "U$5") (pin "P$3") (pinfunction "3_P$3") (pintype "passive"))
      (node (ref "U$5") (pin "P$4") (pinfunction "4_P$4") (pintype "passive"))
      (node (ref "U$5") (pin "P$5") (pinfunction "5_P$5") (pintype "passive"))
      (node (ref "U$5") (pin "P$6") (pinfunction "6_P$6") (pintype "passive"))
      (node (ref "U$9") (pin "DRAIN") (pinfunction "P$1_DRAIN") (pintype "bidirectional"))
    )
    (net (code "54") (name "Net-(U$5-12)") (class "Default")
      (node (ref "D2") (pin "A") (pinfunction "A_A") (pintype "passive"))
      (node (ref "U$5") (pin "P$12") (pinfunction "12_P$12") (pintype "passive"))
    )
    (net (code "55") (name "Net-(U1-K)") (class "Default")
      (node (ref "POWER_HEAD1") (pin "P$1") (pinfunction "P$1_P$1") (pintype "bidirectional"))
      (node (ref "U1") (pin "2") (pinfunction "K_2") (pintype "bidirectional"))
    )
    (net (code "56") (name "Net-(U4-K)") (class "Default")
      (node (ref "U4") (pin "2") (pinfunction "K_2") (pintype "bidirectional"))
      (node (ref "V_BAT") (pin "P$1") (pinfunction "P$1_P$1") (pintype "bidirectional"))
    )
    (net (code "57") (name "unconnected-(IC1-ADC6-Pad19)") (class "Default")
      (node (ref "IC1") (pin "19") (pinfunction "ADC6_19") (pintype "bidirectional"))
    )
    (net (code "58") (name "unconnected-(IC1-ADC7-Pad22)") (class "Default")
      (node (ref "IC1") (pin "22") (pinfunction "ADC7_22") (pintype "bidirectional"))
    )
    (net (code "59") (name "unconnected-(IC1-PC3(ADC3)-Pad26)") (class "Default")
      (node (ref "IC1") (pin "26") (pinfunction "PC3(ADC3)_26") (pintype "bidirectional"))
    )
    (net (code "60") (name "unconnected-(IC1-PC4(ADC4{slash}SDA)-Pad27)") (class "Default")
      (node (ref "IC1") (pin "27") (pinfunction "PC4(ADC4/SDA)_27") (pintype "bidirectional"))
    )
    (net (code "61") (name "unconnected-(IC1-PC5(ADC5{slash}SCL)-Pad28)") (class "Default")
      (node (ref "IC1") (pin "28") (pinfunction "PC5(ADC5/SCL)_28") (pintype "bidirectional"))
    )
    (net (code "62") (name "unconnected-(IC1-PD7(AIN1)-Pad11)") (class "Default")
      (node (ref "IC1") (pin "11") (pinfunction "PD7(AIN1)_11") (pintype "bidirectional"))
    )
    (net (code "63") (name "unconnected-(J5-Pad2)") (class "Default")
      (node (ref "J5") (pin "2") (pinfunction "2_2") (pintype "passive"))
    )
    (net (code "64") (name "unconnected-(J7-Pad2)") (class "Default")
      (node (ref "J7") (pin "2") (pinfunction "2_2") (pintype "passive"))
    )
    (net (code "65") (name "unconnected-(S1A-O-Pad1)") (class "Default")
      (node (ref "S1") (pin "1") (pinfunction "O_1") (pintype "passive"))
    )
    (net (code "66") (name "unconnected-(S1B-O-Pad4)") (class "Default")
      (node (ref "S1") (pin "4") (pinfunction "O_4") (pintype "passive"))
    )
    (net (code "67") (name "unconnected-(U$10-PadNC)") (class "Default")
      (node (ref "U$10") (pin "NC") (pinfunction "NC_NC") (pintype "bidirectional"))
    )
    (net (code "68") (name "unconnected-(U$11-PadNC)") (class "Default")
      (node (ref "U$11") (pin "NC") (pinfunction "NC_NC") (pintype "bidirectional"))
    )
    (net (code "69") (name "unconnected-(U$12-PadNC)") (class "Default")
      (node (ref "U$12") (pin "NC") (pinfunction "NC_NC") (pintype "bidirectional"))
    )
    (net (code "70") (name "unconnected-(U$13-PadNC)") (class "Default")
      (node (ref "U$13") (pin "NC") (pinfunction "NC_NC") (pintype "bidirectional"))
    )
  )
)
